# VFDControl.net
KiCad netlist of a schematic drawn in EAGLE
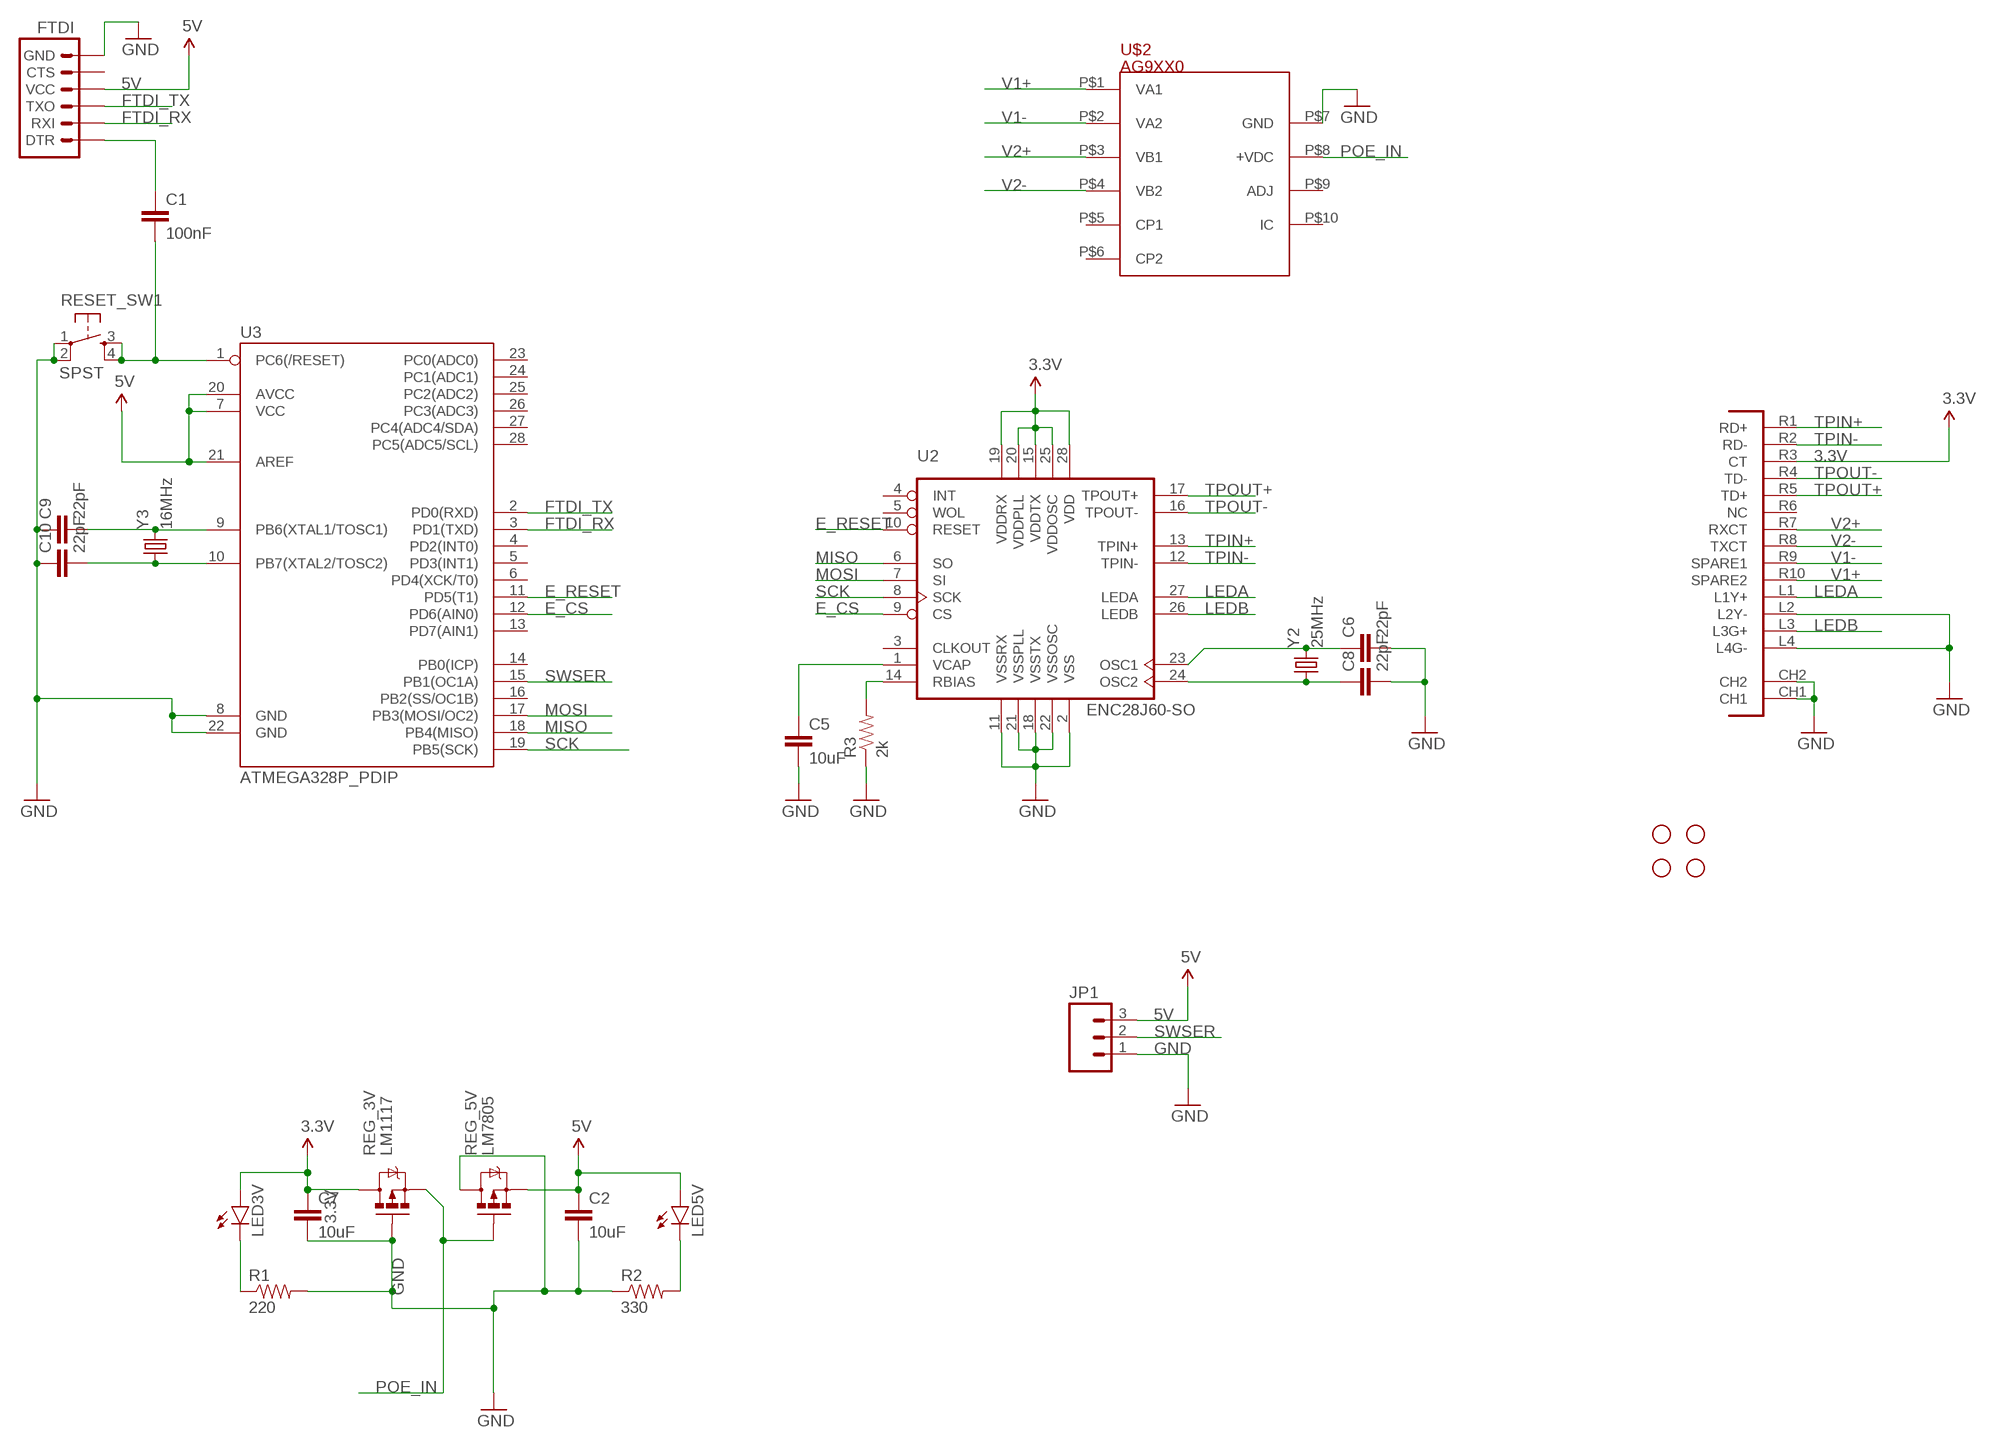
[diagram p0: schematic, sheet 1]

(export (version "E")
  (design (tool "Eeschema 10.0.6"))
  (components
    (comp (ref "C1")
      (value "100nF")
      (footprint "eagle-import:CAP-PTH-SMALL")
      (libsource (lib "eagle-import") (part "CAPPTH"))
    )
    (comp (ref "C2")
      (value "10uF")
      (footprint "eagle-import:CAP-PTH-SMALL")
      (libsource (lib "eagle-import") (part "CAPPTH"))
    )
    (comp (ref "C5")
      (value "10uF")
      (footprint "eagle-import:CAP-PTH-SMALL")
      (libsource (lib "eagle-import") (part "CAPPTH"))
    )
    (comp (ref "C6")
      (value "22pF")
      (footprint "eagle-import:CAP-PTH-SMALL")
      (libsource (lib "eagle-import") (part "CAPPTH"))
    )
    (comp (ref "C7")
      (value "10uF")
      (footprint "eagle-import:CAP-PTH-SMALL")
      (libsource (lib "eagle-import") (part "CAPPTH"))
    )
    (comp (ref "C8")
      (value "22pF")
      (footprint "eagle-import:CAP-PTH-SMALL")
      (libsource (lib "eagle-import") (part "CAPPTH"))
    )
    (comp (ref "C9")
      (value "22pF")
      (footprint "eagle-import:CAP-PTH-SMALL")
      (libsource (lib "eagle-import") (part "CAPPTH"))
    )
    (comp (ref "C10")
      (value "22pF")
      (footprint "eagle-import:CAP-PTH-SMALL")
      (libsource (lib "eagle-import") (part "CAPPTH"))
    )
    (comp (ref "FTDI")
      (value "ARDUINO_SERIAL_PROGRAMPTH")
      (footprint "eagle-import:1X06")
      (libsource (lib "eagle-import") (part "ARDUINO_SERIAL_PROGRAMPTH"))
    )
    (comp (ref "JP1")
      (value "M03PTH")
      (footprint "eagle-import:1X03")
      (libsource (lib "eagle-import") (part "M03PTH"))
    )
    (comp (ref "LED3V")
      (value "LED3MM")
      (footprint "eagle-import:LED3MM")
      (libsource (lib "eagle-import") (part "LED3MM"))
    )
    (comp (ref "LED5V")
      (value "LED3MM")
      (footprint "eagle-import:LED3MM")
      (libsource (lib "eagle-import") (part "LED3MM"))
    )
    (comp (ref "R1")
      (value "220")
      (footprint "eagle-import:AXIAL-0.1")
      (libsource (lib "eagle-import") (part "RESISTORPTH-1/4W-VERT"))
    )
    (comp (ref "R2")
      (value "330")
      (footprint "eagle-import:AXIAL-0.1")
      (libsource (lib "eagle-import") (part "RESISTORPTH-1/4W-VERT"))
    )
    (comp (ref "R3")
      (value "2k")
      (footprint "eagle-import:AXIAL-0.1")
      (libsource (lib "eagle-import") (part "RESISTORPTH-1/4W-VERT"))
    )
    (comp (ref "REG_3V")
      (value "LM1117")
      (footprint "eagle-import:TO220V")
      (libsource (lib "eagle-import") (part "MOSFET-PCHANNELFQP27P06"))
    )
    (comp (ref "REG_5V")
      (value "LM7805")
      (footprint "eagle-import:TO220V")
      (libsource (lib "eagle-import") (part "MOSFET-PCHANNELFQP27P06"))
    )
    (comp (ref "RESET_SW1")
      (value "SPST")
      (footprint "eagle-import:TAC-SWITCH-PTH")
      (libsource (lib "eagle-import") (part "TACTILE-SWITCH-PTH"))
    )
    (comp (ref "STANDOFF1")
      (value "STAND-OFF")
      (footprint "eagle-import:STAND-OFF")
      (libsource (lib "eagle-import") (part "STAND-OFF"))
    )
    (comp (ref "STANDOFF2")
      (value "STAND-OFF")
      (footprint "eagle-import:STAND-OFF")
      (libsource (lib "eagle-import") (part "STAND-OFF"))
    )
    (comp (ref "STANDOFF3")
      (value "STAND-OFF")
      (footprint "eagle-import:STAND-OFF")
      (libsource (lib "eagle-import") (part "STAND-OFF"))
    )
    (comp (ref "STANDOFF4")
      (value "STAND-OFF")
      (footprint "eagle-import:STAND-OFF")
      (libsource (lib "eagle-import") (part "STAND-OFF"))
    )
    (comp (ref "U$2")
      (value "AG9XX0")
      (footprint "eagle-import:AG9000")
      (libsource (lib "eagle-import") (part "AG9XX0"))
    )
    (comp (ref "U$3")
      (value "POE-RJ45")
      (footprint "eagle-import:POE-RJ45")
      (libsource (lib "eagle-import") (part "POE-RJ45"))
    )
    (comp (ref "U2")
      (value "ENC28J60-SO")
      (footprint "eagle-import:SO28W")
      (libsource (lib "eagle-import") (part "ENC28J60-SO"))
    )
    (comp (ref "U3")
      (value "ATMEGA328P_PDIP")
      (footprint "eagle-import:DIL28-3")
      (libsource (lib "eagle-import") (part "ATMEGA328P_PDIP"))
    )
    (comp (ref "Y2")
      (value "25MHz")
      (footprint "eagle-import:HC49US")
      (libsource (lib "eagle-import") (part "CRYSTALHC49US"))
    )
    (comp (ref "Y3")
      (value "16MHz")
      (footprint "eagle-import:HC49US")
      (libsource (lib "eagle-import") (part "CRYSTALHC49US"))
    )
  )
  (nets
    (net (code "1") (name "/E_CS") (class "Default")
      (node (ref "U2") (pin "9") (pinfunction "CS_9") (pintype "input"))
      (node (ref "U3") (pin "12") (pinfunction "PD6(AIN0)_12") (pintype "bidirectional"))
    )
    (net (code "2") (name "/E_RESET") (class "Default")
      (node (ref "U2") (pin "10") (pinfunction "RESET_10") (pintype "input"))
      (node (ref "U3") (pin "11") (pinfunction "PD5(T1)_11") (pintype "bidirectional"))
    )
    (net (code "3") (name "/FTDI_RX") (class "Default")
      (node (ref "FTDI") (pin "2") (pinfunction "RXI_2") (pintype "passive"))
      (node (ref "U3") (pin "3") (pinfunction "PD1(TXD)_3") (pintype "bidirectional"))
    )
    (net (code "4") (name "/FTDI_TX") (class "Default")
      (node (ref "FTDI") (pin "3") (pinfunction "TXO_3") (pintype "passive"))
      (node (ref "U3") (pin "2") (pinfunction "PD0(RXD)_2") (pintype "bidirectional"))
    )
    (net (code "5") (name "/LEDA") (class "Default")
      (node (ref "U$3") (pin "L1") (pinfunction "L1Y+_L1") (pintype "bidirectional"))
      (node (ref "U2") (pin "27") (pinfunction "LEDA_27") (pintype "output"))
    )
    (net (code "6") (name "/LEDB") (class "Default")
      (node (ref "U$3") (pin "L3") (pinfunction "L3G+_L3") (pintype "bidirectional"))
      (node (ref "U2") (pin "26") (pinfunction "LEDB_26") (pintype "output"))
    )
    (net (code "7") (name "/MISO") (class "Default")
      (node (ref "U2") (pin "6") (pinfunction "SO_6") (pintype "output"))
      (node (ref "U3") (pin "18") (pinfunction "PB4(MISO)_18") (pintype "bidirectional"))
    )
    (net (code "8") (name "/MOSI") (class "Default")
      (node (ref "U2") (pin "7") (pinfunction "SI_7") (pintype "input"))
      (node (ref "U3") (pin "17") (pinfunction "PB3(MOSI/OC2)_17") (pintype "bidirectional"))
    )
    (net (code "9") (name "/POE_IN") (class "Default")
      (node (ref "REG_3V") (pin "3") (pinfunction "S_3") (pintype "passive"))
      (node (ref "REG_5V") (pin "1") (pinfunction "G_1") (pintype "passive"))
      (node (ref "U$2") (pin "P$8") (pinfunction "+VDC_P$8") (pintype "power_in"))
    )
    (net (code "10") (name "/SCK") (class "Default")
      (node (ref "U2") (pin "8") (pinfunction "SCK_8") (pintype "input"))
      (node (ref "U3") (pin "19") (pinfunction "PB5(SCK)_19") (pintype "bidirectional"))
    )
    (net (code "11") (name "/SWSER") (class "Default")
      (node (ref "JP1") (pin "2") (pinfunction "2_2") (pintype "passive"))
      (node (ref "U3") (pin "15") (pinfunction "PB1(OC1A)_15") (pintype "bidirectional"))
    )
    (net (code "12") (name "/TPIN+") (class "Default")
      (node (ref "U$3") (pin "R1") (pinfunction "RD+_R1") (pintype "bidirectional"))
      (node (ref "U2") (pin "13") (pinfunction "TPIN+_13") (pintype "input"))
    )
    (net (code "13") (name "/TPIN-") (class "Default")
      (node (ref "U$3") (pin "R2") (pinfunction "RD-_R2") (pintype "bidirectional"))
      (node (ref "U2") (pin "12") (pinfunction "TPIN-_12") (pintype "input"))
    )
    (net (code "14") (name "/TPOUT+") (class "Default")
      (node (ref "U$3") (pin "R5") (pinfunction "TD+_R5") (pintype "bidirectional"))
      (node (ref "U2") (pin "17") (pinfunction "TPOUT+_17") (pintype "output"))
    )
    (net (code "15") (name "/TPOUT-") (class "Default")
      (node (ref "U$3") (pin "R4") (pinfunction "TD-_R4") (pintype "bidirectional"))
      (node (ref "U2") (pin "16") (pinfunction "TPOUT-_16") (pintype "output"))
    )
    (net (code "16") (name "/V1+") (class "Default")
      (node (ref "U$2") (pin "P$1") (pinfunction "VA1_P$1") (pintype "input"))
      (node (ref "U$3") (pin "R10") (pinfunction "SPARE2_R10") (pintype "bidirectional"))
    )
    (net (code "17") (name "/V1-") (class "Default")
      (node (ref "U$2") (pin "P$2") (pinfunction "VA2_P$2") (pintype "input"))
      (node (ref "U$3") (pin "R9") (pinfunction "SPARE1_R9") (pintype "bidirectional"))
    )
    (net (code "18") (name "/V2+") (class "Default")
      (node (ref "U$2") (pin "P$3") (pinfunction "VB1_P$3") (pintype "input"))
      (node (ref "U$3") (pin "R7") (pinfunction "RXCT_R7") (pintype "bidirectional"))
    )
    (net (code "19") (name "/V2-") (class "Default")
      (node (ref "U$2") (pin "P$4") (pinfunction "VB2_P$4") (pintype "input"))
      (node (ref "U$3") (pin "R8") (pinfunction "TXCT_R8") (pintype "bidirectional"))
    )
    (net (code "20") (name "3.3V") (class "Default")
      (node (ref "C7") (pin "1") (pinfunction "1_1") (pintype "passive"))
      (node (ref "LED3V") (pin "A") (pinfunction "A_A") (pintype "passive"))
      (node (ref "REG_3V") (pin "2") (pinfunction "D_2") (pintype "passive"))
      (node (ref "U$3") (pin "R3") (pinfunction "CT_R3") (pintype "bidirectional"))
      (node (ref "U2") (pin "15") (pinfunction "VDDTX_15") (pintype "power_in"))
      (node (ref "U2") (pin "19") (pinfunction "VDDRX_19") (pintype "power_in"))
      (node (ref "U2") (pin "20") (pinfunction "VDDPLL_20") (pintype "power_in"))
      (node (ref "U2") (pin "25") (pinfunction "VDDOSC_25") (pintype "power_in"))
      (node (ref "U2") (pin "28") (pinfunction "VDD_28") (pintype "power_in"))
    )
    (net (code "21") (name "5V") (class "Default")
      (node (ref "C2") (pin "1") (pinfunction "1_1") (pintype "passive"))
      (node (ref "FTDI") (pin "4") (pinfunction "VCC_4") (pintype "passive"))
      (node (ref "JP1") (pin "3") (pinfunction "3_3") (pintype "passive"))
      (node (ref "LED5V") (pin "A") (pinfunction "A_A") (pintype "passive"))
      (node (ref "REG_5V") (pin "3") (pinfunction "S_3") (pintype "passive"))
      (node (ref "U3") (pin "20") (pinfunction "AVCC_20") (pintype "bidirectional"))
      (node (ref "U3") (pin "21") (pinfunction "AREF_21") (pintype "bidirectional"))
      (node (ref "U3") (pin "7") (pinfunction "VCC_7") (pintype "bidirectional"))
    )
    (net (code "22") (name "GND") (class "Default")
      (node (ref "C10") (pin "1") (pinfunction "1_1") (pintype "passive"))
      (node (ref "C2") (pin "2") (pinfunction "2_2") (pintype "passive"))
      (node (ref "C5") (pin "2") (pinfunction "2_2") (pintype "passive"))
      (node (ref "C6") (pin "2") (pinfunction "2_2") (pintype "passive"))
      (node (ref "C7") (pin "2") (pinfunction "2_2") (pintype "passive"))
      (node (ref "C8") (pin "2") (pinfunction "2_2") (pintype "passive"))
      (node (ref "C9") (pin "1") (pinfunction "1_1") (pintype "passive"))
      (node (ref "FTDI") (pin "6") (pinfunction "GND_6") (pintype "passive"))
      (node (ref "JP1") (pin "1") (pinfunction "1_1") (pintype "passive"))
      (node (ref "R1") (pin "P$2") (pinfunction "2_P$2") (pintype "passive"))
      (node (ref "R2") (pin "P$1") (pinfunction "1_P$1") (pintype "passive"))
      (node (ref "R3") (pin "P$1") (pinfunction "1_P$1") (pintype "passive"))
      (node (ref "REG_3V") (pin "1") (pinfunction "G_1") (pintype "passive"))
      (node (ref "REG_5V") (pin "2") (pinfunction "D_2") (pintype "passive"))
      (node (ref "RESET_SW1") (pin "1") (pinfunction "1_1") (pintype "passive"))
      (node (ref "RESET_SW1") (pin "2") (pinfunction "2_2") (pintype "passive"))
      (node (ref "U$2") (pin "P$7") (pinfunction "GND_P$7") (pintype "power_in"))
      (node (ref "U$3") (pin "CH1") (pinfunction "CH1_CH1") (pintype "bidirectional"))
      (node (ref "U$3") (pin "CH2") (pinfunction "CH2_CH2") (pintype "bidirectional"))
      (node (ref "U$3") (pin "L2") (pinfunction "L2Y-_L2") (pintype "bidirectional"))
      (node (ref "U$3") (pin "L4") (pinfunction "L4G-_L4") (pintype "bidirectional"))
      (node (ref "U2") (pin "11") (pinfunction "VSSRX_11") (pintype "power_in"))
      (node (ref "U2") (pin "18") (pinfunction "VSSTX_18") (pintype "power_in"))
      (node (ref "U2") (pin "2") (pinfunction "VSS_2") (pintype "power_in"))
      (node (ref "U2") (pin "21") (pinfunction "VSSPLL_21") (pintype "power_in"))
      (node (ref "U2") (pin "22") (pinfunction "VSSOSC_22") (pintype "power_in"))
      (node (ref "U3") (pin "22") (pinfunction "GND_22") (pintype "bidirectional"))
      (node (ref "U3") (pin "8") (pinfunction "GND_8") (pintype "bidirectional"))
    )
    (net (code "23") (name "Net-(FTDI-DTR)") (class "Default")
      (node (ref "C1") (pin "1") (pinfunction "1_1") (pintype "passive"))
      (node (ref "FTDI") (pin "1") (pinfunction "DTR_1") (pintype "passive"))
    )
    (net (code "24") (name "Net-(LED3V-C)") (class "Default")
      (node (ref "LED3V") (pin "K") (pinfunction "C_K") (pintype "passive"))
      (node (ref "R1") (pin "P$1") (pinfunction "1_P$1") (pintype "passive"))
    )
    (net (code "25") (name "Net-(LED5V-C)") (class "Default")
      (node (ref "LED5V") (pin "K") (pinfunction "C_K") (pintype "passive"))
      (node (ref "R2") (pin "P$2") (pinfunction "2_P$2") (pintype "passive"))
    )
    (net (code "26") (name "Net-(R3-2)") (class "Default")
      (node (ref "R3") (pin "P$2") (pinfunction "2_P$2") (pintype "passive"))
      (node (ref "U2") (pin "14") (pinfunction "RBIAS_14") (pintype "passive"))
    )
    (net (code "27") (name "Net-(U2-OSC1)") (class "Default")
      (node (ref "C6") (pin "1") (pinfunction "1_1") (pintype "passive"))
      (node (ref "U2") (pin "23") (pinfunction "OSC1_23") (pintype "input"))
      (node (ref "Y2") (pin "2") (pinfunction "2_2") (pintype "passive"))
    )
    (net (code "28") (name "Net-(U2-OSC2)") (class "Default")
      (node (ref "C8") (pin "1") (pinfunction "1_1") (pintype "passive"))
      (node (ref "U2") (pin "24") (pinfunction "OSC2_24") (pintype "output"))
      (node (ref "Y2") (pin "1") (pinfunction "1_1") (pintype "passive"))
    )
    (net (code "29") (name "Net-(U2-VCAP)") (class "Default")
      (node (ref "C5") (pin "1") (pinfunction "1_1") (pintype "passive"))
      (node (ref "U2") (pin "1") (pinfunction "VCAP_1") (pintype "power_in"))
    )
    (net (code "30") (name "Net-(U3-PB6(XTAL1{slash}TOSC1))") (class "Default")
      (node (ref "C9") (pin "2") (pinfunction "2_2") (pintype "passive"))
      (node (ref "U3") (pin "9") (pinfunction "PB6(XTAL1/TOSC1)_9") (pintype "bidirectional"))
      (node (ref "Y3") (pin "2") (pinfunction "2_2") (pintype "passive"))
    )
    (net (code "31") (name "Net-(U3-PB7(XTAL2{slash}TOSC2))") (class "Default")
      (node (ref "C10") (pin "2") (pinfunction "2_2") (pintype "passive"))
      (node (ref "U3") (pin "10") (pinfunction "PB7(XTAL2/TOSC2)_10") (pintype "bidirectional"))
      (node (ref "Y3") (pin "1") (pinfunction "1_1") (pintype "passive"))
    )
    (net (code "32") (name "Net-(U3-PC6({slash}RESET))") (class "Default")
      (node (ref "C1") (pin "2") (pinfunction "2_2") (pintype "passive"))
      (node (ref "RESET_SW1") (pin "3") (pinfunction "3_3") (pintype "passive"))
      (node (ref "RESET_SW1") (pin "4") (pinfunction "4_4") (pintype "passive"))
      (node (ref "U3") (pin "1") (pinfunction "PC6(/RESET)_1") (pintype "bidirectional"))
    )
    (net (code "33") (name "unconnected-(FTDI-CTS-Pad5)") (class "Default")
      (node (ref "FTDI") (pin "5") (pinfunction "CTS_5") (pintype "passive"))
    )
    (net (code "34") (name "unconnected-(U$2-ADJ-PadP$9)") (class "Default")
      (node (ref "U$2") (pin "P$9") (pinfunction "ADJ_P$9") (pintype "passive"))
    )
    (net (code "35") (name "unconnected-(U$2-CP1-PadP$5)") (class "Default")
      (node (ref "U$2") (pin "P$5") (pinfunction "CP1_P$5") (pintype "input"))
    )
    (net (code "36") (name "unconnected-(U$2-CP2-PadP$6)") (class "Default")
      (node (ref "U$2") (pin "P$6") (pinfunction "CP2_P$6") (pintype "input"))
    )
    (net (code "37") (name "unconnected-(U$2-IC-PadP$10)") (class "Default")
      (node (ref "U$2") (pin "P$10") (pinfunction "IC_P$10") (pintype "no_connect"))
    )
    (net (code "38") (name "unconnected-(U$3-NC-PadR6)") (class "Default")
      (node (ref "U$3") (pin "R6") (pinfunction "NC_R6") (pintype "bidirectional"))
    )
    (net (code "39") (name "unconnected-(U2-CLKOUT-Pad3)") (class "Default")
      (node (ref "U2") (pin "3") (pinfunction "CLKOUT_3") (pintype "output"))
    )
    (net (code "40") (name "unconnected-(U2-INT-Pad4)") (class "Default")
      (node (ref "U2") (pin "4") (pinfunction "INT_4") (pintype "output"))
    )
    (net (code "41") (name "unconnected-(U2-WOL-Pad5)") (class "Default")
      (node (ref "U2") (pin "5") (pinfunction "WOL_5") (pintype "output"))
    )
    (net (code "42") (name "unconnected-(U3-PB0(ICP)-Pad14)") (class "Default")
      (node (ref "U3") (pin "14") (pinfunction "PB0(ICP)_14") (pintype "bidirectional"))
    )
    (net (code "43") (name "unconnected-(U3-PB2(SS{slash}OC1B)-Pad16)") (class "Default")
      (node (ref "U3") (pin "16") (pinfunction "PB2(SS/OC1B)_16") (pintype "bidirectional"))
    )
    (net (code "44") (name "unconnected-(U3-PC0(ADC0)-Pad23)") (class "Default")
      (node (ref "U3") (pin "23") (pinfunction "PC0(ADC0)_23") (pintype "bidirectional"))
    )
    (net (code "45") (name "unconnected-(U3-PC1(ADC1)-Pad24)") (class "Default")
      (node (ref "U3") (pin "24") (pinfunction "PC1(ADC1)_24") (pintype "bidirectional"))
    )
    (net (code "46") (name "unconnected-(U3-PC2(ADC2)-Pad25)") (class "Default")
      (node (ref "U3") (pin "25") (pinfunction "PC2(ADC2)_25") (pintype "bidirectional"))
    )
    (net (code "47") (name "unconnected-(U3-PC3(ADC3)-Pad26)") (class "Default")
      (node (ref "U3") (pin "26") (pinfunction "PC3(ADC3)_26") (pintype "bidirectional"))
    )
    (net (code "48") (name "unconnected-(U3-PC4(ADC4{slash}SDA)-Pad27)") (class "Default")
      (node (ref "U3") (pin "27") (pinfunction "PC4(ADC4/SDA)_27") (pintype "bidirectional"))
    )
    (net (code "49") (name "unconnected-(U3-PC5(ADC5{slash}SCL)-Pad28)") (class "Default")
      (node (ref "U3") (pin "28") (pinfunction "PC5(ADC5/SCL)_28") (pintype "bidirectional"))
    )
    (net (code "50") (name "unconnected-(U3-PD2(INT0)-Pad4)") (class "Default")
      (node (ref "U3") (pin "4") (pinfunction "PD2(INT0)_4") (pintype "bidirectional"))
    )
    (net (code "51") (name "unconnected-(U3-PD3(INT1)-Pad5)") (class "Default")
      (node (ref "U3") (pin "5") (pinfunction "PD3(INT1)_5") (pintype "bidirectional"))
    )
    (net (code "52") (name "unconnected-(U3-PD4(XCK{slash}T0)-Pad6)") (class "Default")
      (node (ref "U3") (pin "6") (pinfunction "PD4(XCK/T0)_6") (pintype "bidirectional"))
    )
    (net (code "53") (name "unconnected-(U3-PD7(AIN1)-Pad13)") (class "Default")
      (node (ref "U3") (pin "13") (pinfunction "PD7(AIN1)_13") (pintype "bidirectional"))
    )
  )
)
